# pcb.net
KiCad netlist of a schematic drawn in EAGLE
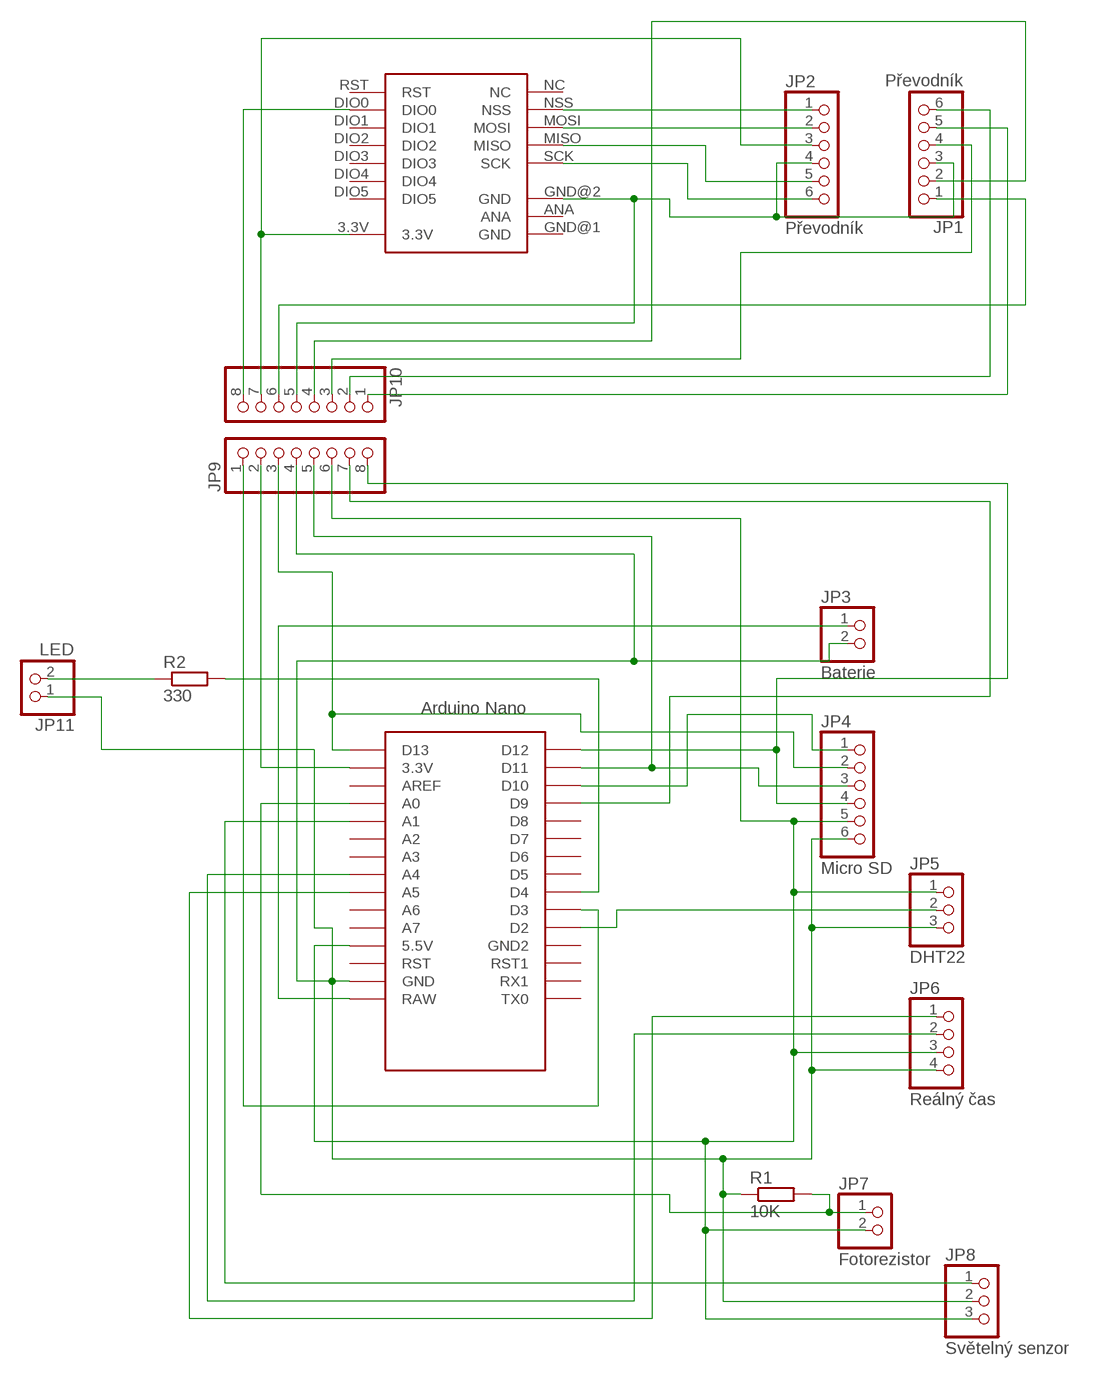
[diagram p0: schematic, sheet 1]

(export (version "E")
  (design (tool "Eeschema 10.0.6"))
  (components
    (comp (ref "JP1")
      (value "Převodník")
      (footprint "eagle-import:1X06")
      (libsource (lib "eagle-import") (part "PINHD-1X6"))
    )
    (comp (ref "JP2")
      (value "Převodník")
      (footprint "eagle-import:1X06")
      (libsource (lib "eagle-import") (part "PINHD-1X6"))
    )
    (comp (ref "JP3")
      (value "Baterie")
      (footprint "eagle-import:1X02")
      (libsource (lib "eagle-import") (part "PINHD-1X2"))
    )
    (comp (ref "JP4")
      (value "Micro SD")
      (footprint "eagle-import:1X06")
      (libsource (lib "eagle-import") (part "PINHD-1X6"))
    )
    (comp (ref "JP5")
      (value "DHT22")
      (footprint "eagle-import:1X03")
      (libsource (lib "eagle-import") (part "PINHD-1X3"))
    )
    (comp (ref "JP6")
      (value "Reálný čas")
      (footprint "eagle-import:1X04")
      (libsource (lib "eagle-import") (part "PINHD-1X4"))
    )
    (comp (ref "JP7")
      (value "Fotorezistor")
      (footprint "eagle-import:1X02")
      (libsource (lib "eagle-import") (part "PINHD-1X2"))
    )
    (comp (ref "JP8")
      (value "Světelný senzor")
      (footprint "eagle-import:1X03")
      (libsource (lib "eagle-import") (part "PINHD-1X3"))
    )
    (comp (ref "JP9")
      (value "PINHD-1X8")
      (footprint "eagle-import:1X08")
      (libsource (lib "eagle-import") (part "PINHD-1X8"))
    )
    (comp (ref "JP10")
      (value "PINHD-1X8")
      (footprint "eagle-import:1X08")
      (libsource (lib "eagle-import") (part "PINHD-1X8"))
    )
    (comp (ref "JP11")
      (value "LED")
      (footprint "eagle-import:1X02")
      (libsource (lib "eagle-import") (part "PINHD-1X2"))
    )
    (comp (ref "R1")
      (value "10K")
      (footprint "eagle-import:0204_7")
      (libsource (lib "eagle-import") (part "R-EU_0204/7"))
    )
    (comp (ref "R2")
      (value "330")
      (footprint "eagle-import:0204_7")
      (libsource (lib "eagle-import") (part "R-EU_0204/7"))
    )
    (comp (ref "RFM69")
      (value "RFM69")
      (footprint "eagle-import:20X16BOARD")
      (libsource (lib "eagle-import") (part "RFM69"))
    )
    (comp (ref "U$1")
      (value "NANO")
      (footprint "eagle-import:NANO")
      (libsource (lib "eagle-import") (part "NANO"))
    )
  )
  (nets
    (net (code "1") (name "/GND") (class "Default")
      (node (ref "RFM69") (pin "GND@1") (pinfunction "GND_GND@1") (pintype "power_in"))
    )
    (net (code "2") (name "/NC") (class "Default")
      (node (ref "RFM69") (pin "NC") (pinfunction "NC_NC") (pintype "power_in"))
    )
    (net (code "3") (name "Net-(JP1-Pad1)") (class "Default")
      (node (ref "JP1") (pin "1") (pinfunction "1_1") (pintype "passive"))
      (node (ref "JP10") (pin "6") (pinfunction "6_6") (pintype "passive"))
    )
    (net (code "4") (name "Net-(JP1-Pad2)") (class "Default")
      (node (ref "JP1") (pin "2") (pinfunction "2_2") (pintype "passive"))
      (node (ref "JP10") (pin "4") (pinfunction "4_4") (pintype "passive"))
    )
    (net (code "5") (name "Net-(JP1-Pad3)") (class "Default")
      (node (ref "JP1") (pin "3") (pinfunction "3_3") (pintype "passive"))
      (node (ref "JP10") (pin "5") (pinfunction "5_5") (pintype "passive"))
      (node (ref "JP2") (pin "4") (pinfunction "4_4") (pintype "passive"))
      (node (ref "RFM69") (pin "GND@2") (pinfunction "GND_GND@2") (pintype "power_in"))
    )
    (net (code "6") (name "Net-(JP1-Pad4)") (class "Default")
      (node (ref "JP1") (pin "4") (pinfunction "4_4") (pintype "passive"))
      (node (ref "JP10") (pin "3") (pinfunction "3_3") (pintype "passive"))
    )
    (net (code "7") (name "Net-(JP1-Pad5)") (class "Default")
      (node (ref "JP1") (pin "5") (pinfunction "5_5") (pintype "passive"))
      (node (ref "JP10") (pin "1") (pinfunction "1_1") (pintype "passive"))
    )
    (net (code "8") (name "Net-(JP1-Pad6)") (class "Default")
      (node (ref "JP1") (pin "6") (pinfunction "6_6") (pintype "passive"))
      (node (ref "JP10") (pin "2") (pinfunction "2_2") (pintype "passive"))
    )
    (net (code "9") (name "Net-(JP2-Pad1)") (class "Default")
      (node (ref "JP2") (pin "1") (pinfunction "1_1") (pintype "passive"))
      (node (ref "RFM69") (pin "NSS") (pinfunction "NSS_NSS") (pintype "bidirectional"))
    )
    (net (code "10") (name "Net-(JP2-Pad2)") (class "Default")
      (node (ref "JP2") (pin "2") (pinfunction "2_2") (pintype "passive"))
      (node (ref "RFM69") (pin "MOSI") (pinfunction "MOSI_MOSI") (pintype "bidirectional"))
    )
    (net (code "11") (name "Net-(JP2-Pad5)") (class "Default")
      (node (ref "JP2") (pin "5") (pinfunction "5_5") (pintype "passive"))
      (node (ref "RFM69") (pin "MISO") (pinfunction "MISO_MISO") (pintype "bidirectional"))
    )
    (net (code "12") (name "Net-(JP2-Pad6)") (class "Default")
      (node (ref "JP2") (pin "6") (pinfunction "6_6") (pintype "passive"))
      (node (ref "RFM69") (pin "SCK") (pinfunction "SCK_SCK") (pintype "bidirectional"))
    )
    (net (code "13") (name "Net-(JP3-Pad1)") (class "Default")
      (node (ref "JP3") (pin "1") (pinfunction "1_1") (pintype "passive"))
      (node (ref "U$1") (pin "RAW") (pinfunction "RAW_RAW") (pintype "bidirectional"))
    )
    (net (code "14") (name "Net-(JP4-Pad1)") (class "Default")
      (node (ref "JP4") (pin "1") (pinfunction "1_1") (pintype "passive"))
      (node (ref "U$1") (pin "D10") (pinfunction "D10_D10") (pintype "bidirectional"))
    )
    (net (code "15") (name "Net-(JP4-Pad2)") (class "Default")
      (node (ref "JP4") (pin "2") (pinfunction "2_2") (pintype "passive"))
      (node (ref "JP9") (pin "3") (pinfunction "3_3") (pintype "passive"))
      (node (ref "U$1") (pin "D13") (pinfunction "D13_D13") (pintype "bidirectional"))
    )
    (net (code "16") (name "Net-(JP4-Pad3)") (class "Default")
      (node (ref "JP4") (pin "3") (pinfunction "3_3") (pintype "passive"))
      (node (ref "JP9") (pin "5") (pinfunction "5_5") (pintype "passive"))
      (node (ref "U$1") (pin "D11") (pinfunction "D11_D11") (pintype "bidirectional"))
    )
    (net (code "17") (name "Net-(JP4-Pad4)") (class "Default")
      (node (ref "JP4") (pin "4") (pinfunction "4_4") (pintype "passive"))
      (node (ref "JP9") (pin "8") (pinfunction "8_8") (pintype "passive"))
      (node (ref "U$1") (pin "D12") (pinfunction "D12_D12") (pintype "bidirectional"))
    )
    (net (code "18") (name "Net-(JP5-Pad2)") (class "Default")
      (node (ref "JP5") (pin "2") (pinfunction "2_2") (pintype "passive"))
      (node (ref "U$1") (pin "D2") (pinfunction "D2_D2") (pintype "bidirectional"))
    )
    (net (code "19") (name "Net-(JP6-Pad1)") (class "Default")
      (node (ref "JP6") (pin "1") (pinfunction "1_1") (pintype "passive"))
      (node (ref "U$1") (pin "A5") (pinfunction "A5_A5") (pintype "bidirectional"))
    )
    (net (code "20") (name "Net-(JP6-Pad2)") (class "Default")
      (node (ref "JP6") (pin "2") (pinfunction "2_2") (pintype "passive"))
      (node (ref "U$1") (pin "A4") (pinfunction "A4_A4") (pintype "bidirectional"))
    )
    (net (code "21") (name "Net-(JP7-Pad1)") (class "Default")
      (node (ref "JP7") (pin "1") (pinfunction "1_1") (pintype "passive"))
      (node (ref "R1") (pin "2") (pinfunction "2_2") (pintype "passive"))
      (node (ref "U$1") (pin "A0") (pinfunction "A0_A0") (pintype "bidirectional"))
    )
    (net (code "22") (name "Net-(JP8-Pad1)") (class "Default")
      (node (ref "JP8") (pin "1") (pinfunction "1_1") (pintype "passive"))
      (node (ref "U$1") (pin "A1") (pinfunction "A1_A1") (pintype "bidirectional"))
    )
    (net (code "23") (name "Net-(JP9-Pad1)") (class "Default")
      (node (ref "JP9") (pin "1") (pinfunction "1_1") (pintype "passive"))
      (node (ref "U$1") (pin "D3") (pinfunction "D3_D3") (pintype "bidirectional"))
    )
    (net (code "24") (name "Net-(JP9-Pad2)") (class "Default")
      (node (ref "JP9") (pin "2") (pinfunction "2_2") (pintype "passive"))
      (node (ref "U$1") (pin "3.3V") (pinfunction "3.3V_3.3V") (pintype "bidirectional"))
    )
    (net (code "25") (name "Net-(JP9-Pad7)") (class "Default")
      (node (ref "JP9") (pin "7") (pinfunction "7_7") (pintype "passive"))
      (node (ref "U$1") (pin "D9") (pinfunction "D9_D9") (pintype "bidirectional"))
    )
    (net (code "26") (name "Net-(JP10-Pad7)") (class "Default")
      (node (ref "JP10") (pin "7") (pinfunction "7_7") (pintype "passive"))
      (node (ref "JP2") (pin "3") (pinfunction "3_3") (pintype "passive"))
      (node (ref "RFM69") (pin "3.3V") (pinfunction "3.3V_3.3V") (pintype "power_in"))
    )
    (net (code "27") (name "Net-(JP10-Pad8)") (class "Default")
      (node (ref "JP10") (pin "8") (pinfunction "8_8") (pintype "passive"))
      (node (ref "RFM69") (pin "DIO0") (pinfunction "DIO0_DIO0") (pintype "bidirectional"))
    )
    (net (code "28") (name "Net-(JP11-Pad1)") (class "Default")
      (node (ref "JP11") (pin "1") (pinfunction "1_1") (pintype "passive"))
      (node (ref "JP3") (pin "2") (pinfunction "2_2") (pintype "passive"))
      (node (ref "JP4") (pin "6") (pinfunction "6_6") (pintype "passive"))
      (node (ref "JP5") (pin "3") (pinfunction "3_3") (pintype "passive"))
      (node (ref "JP6") (pin "4") (pinfunction "4_4") (pintype "passive"))
      (node (ref "JP8") (pin "2") (pinfunction "2_2") (pintype "passive"))
      (node (ref "JP9") (pin "4") (pinfunction "4_4") (pintype "passive"))
      (node (ref "R1") (pin "1") (pinfunction "1_1") (pintype "passive"))
      (node (ref "U$1") (pin "GND") (pinfunction "GND_GND") (pintype "bidirectional"))
    )
    (net (code "29") (name "Net-(JP11-Pad2)") (class "Default")
      (node (ref "JP11") (pin "2") (pinfunction "2_2") (pintype "passive"))
      (node (ref "R2") (pin "1") (pinfunction "1_1") (pintype "passive"))
    )
    (net (code "30") (name "Net-(R2-Pad2)") (class "Default")
      (node (ref "R2") (pin "2") (pinfunction "2_2") (pintype "passive"))
      (node (ref "U$1") (pin "D4") (pinfunction "D4_D4") (pintype "bidirectional"))
    )
    (net (code "31") (name "Net-(U$1-5.5V)") (class "Default")
      (node (ref "JP4") (pin "5") (pinfunction "5_5") (pintype "passive"))
      (node (ref "JP5") (pin "1") (pinfunction "1_1") (pintype "passive"))
      (node (ref "JP6") (pin "3") (pinfunction "3_3") (pintype "passive"))
      (node (ref "JP7") (pin "2") (pinfunction "2_2") (pintype "passive"))
      (node (ref "JP8") (pin "3") (pinfunction "3_3") (pintype "passive"))
      (node (ref "JP9") (pin "6") (pinfunction "6_6") (pintype "passive"))
      (node (ref "U$1") (pin "5V") (pinfunction "5.5V_5V") (pintype "bidirectional"))
    )
    (net (code "32") (name "unconnected-(RFM69-PadANA)") (class "Default")
      (node (ref "RFM69") (pin "ANA") (pinfunction "ANA_ANA") (pintype "bidirectional"))
    )
    (net (code "33") (name "unconnected-(RFM69-PadDIO1)") (class "Default")
      (node (ref "RFM69") (pin "DIO1") (pinfunction "DIO1_DIO1") (pintype "bidirectional"))
    )
    (net (code "34") (name "unconnected-(RFM69-PadDIO2)") (class "Default")
      (node (ref "RFM69") (pin "DIO2") (pinfunction "DIO2_DIO2") (pintype "bidirectional"))
    )
    (net (code "35") (name "unconnected-(RFM69-PadDIO3)") (class "Default")
      (node (ref "RFM69") (pin "DIO3") (pinfunction "DIO3_DIO3") (pintype "bidirectional"))
    )
    (net (code "36") (name "unconnected-(RFM69-PadDIO4)") (class "Default")
      (node (ref "RFM69") (pin "DIO4") (pinfunction "DIO4_DIO4") (pintype "bidirectional"))
    )
    (net (code "37") (name "unconnected-(RFM69-PadDIO5)") (class "Default")
      (node (ref "RFM69") (pin "DIO5") (pinfunction "DIO5_DIO5") (pintype "bidirectional"))
    )
    (net (code "38") (name "unconnected-(RFM69-PadRST)") (class "Default")
      (node (ref "RFM69") (pin "RST") (pinfunction "RST_RST") (pintype "bidirectional"))
    )
    (net (code "39") (name "unconnected-(U$1-GND2-PadGND1)") (class "Default")
      (node (ref "U$1") (pin "GND1") (pinfunction "GND2_GND1") (pintype "bidirectional"))
    )
    (net (code "40") (name "unconnected-(U$1-PadA2)") (class "Default")
      (node (ref "U$1") (pin "A2") (pinfunction "A2_A2") (pintype "bidirectional"))
    )
    (net (code "41") (name "unconnected-(U$1-PadA3)") (class "Default")
      (node (ref "U$1") (pin "A3") (pinfunction "A3_A3") (pintype "bidirectional"))
    )
    (net (code "42") (name "unconnected-(U$1-PadA6)") (class "Default")
      (node (ref "U$1") (pin "A6") (pinfunction "A6_A6") (pintype "bidirectional"))
    )
    (net (code "43") (name "unconnected-(U$1-PadA7)") (class "Default")
      (node (ref "U$1") (pin "A7") (pinfunction "A7_A7") (pintype "bidirectional"))
    )
    (net (code "44") (name "unconnected-(U$1-PadAREF)") (class "Default")
      (node (ref "U$1") (pin "AREF") (pinfunction "AREF_AREF") (pintype "bidirectional"))
    )
    (net (code "45") (name "unconnected-(U$1-PadD5)") (class "Default")
      (node (ref "U$1") (pin "D5") (pinfunction "D5_D5") (pintype "bidirectional"))
    )
    (net (code "46") (name "unconnected-(U$1-PadD6)") (class "Default")
      (node (ref "U$1") (pin "D6") (pinfunction "D6_D6") (pintype "bidirectional"))
    )
    (net (code "47") (name "unconnected-(U$1-PadD7)") (class "Default")
      (node (ref "U$1") (pin "D7") (pinfunction "D7_D7") (pintype "bidirectional"))
    )
    (net (code "48") (name "unconnected-(U$1-PadD8)") (class "Default")
      (node (ref "U$1") (pin "D8") (pinfunction "D8_D8") (pintype "bidirectional"))
    )
    (net (code "49") (name "unconnected-(U$1-PadICSP1)") (class "Default")
      (node (ref "U$1") (pin "ICSP1") (pinfunction "ICSP1_ICSP1") (pintype "bidirectional"))
    )
    (net (code "50") (name "unconnected-(U$1-PadICSP2)") (class "Default")
      (node (ref "U$1") (pin "ICSP2") (pinfunction "ICSP2_ICSP2") (pintype "bidirectional"))
    )
    (net (code "51") (name "unconnected-(U$1-PadICSP3)") (class "Default")
      (node (ref "U$1") (pin "ICSP3") (pinfunction "ICSP3_ICSP3") (pintype "bidirectional"))
    )
    (net (code "52") (name "unconnected-(U$1-PadICSP4)") (class "Default")
      (node (ref "U$1") (pin "ICSP4") (pinfunction "ICSP4_ICSP4") (pintype "bidirectional"))
    )
    (net (code "53") (name "unconnected-(U$1-PadICSP5)") (class "Default")
      (node (ref "U$1") (pin "ICSP5") (pinfunction "ICSP5_ICSP5") (pintype "bidirectional"))
    )
    (net (code "54") (name "unconnected-(U$1-PadICSP6)") (class "Default")
      (node (ref "U$1") (pin "ICSP6") (pinfunction "ICSP6_ICSP6") (pintype "bidirectional"))
    )
    (net (code "55") (name "unconnected-(U$1-PadRST)") (class "Default")
      (node (ref "U$1") (pin "RST") (pinfunction "RST_RST") (pintype "bidirectional"))
    )
    (net (code "56") (name "unconnected-(U$1-PadRST1)") (class "Default")
      (node (ref "U$1") (pin "RST1") (pinfunction "RST1_RST1") (pintype "bidirectional"))
    )
    (net (code "57") (name "unconnected-(U$1-PadRX1)") (class "Default")
      (node (ref "U$1") (pin "RX1") (pinfunction "RX1_RX1") (pintype "bidirectional"))
    )
    (net (code "58") (name "unconnected-(U$1-PadTX0)") (class "Default")
      (node (ref "U$1") (pin "TX0") (pinfunction "TX0_TX0") (pintype "bidirectional"))
    )
  )
)
